# Battery_Gauge_Main_Board.net
KiCad netlist of a schematic drawn in EAGLE
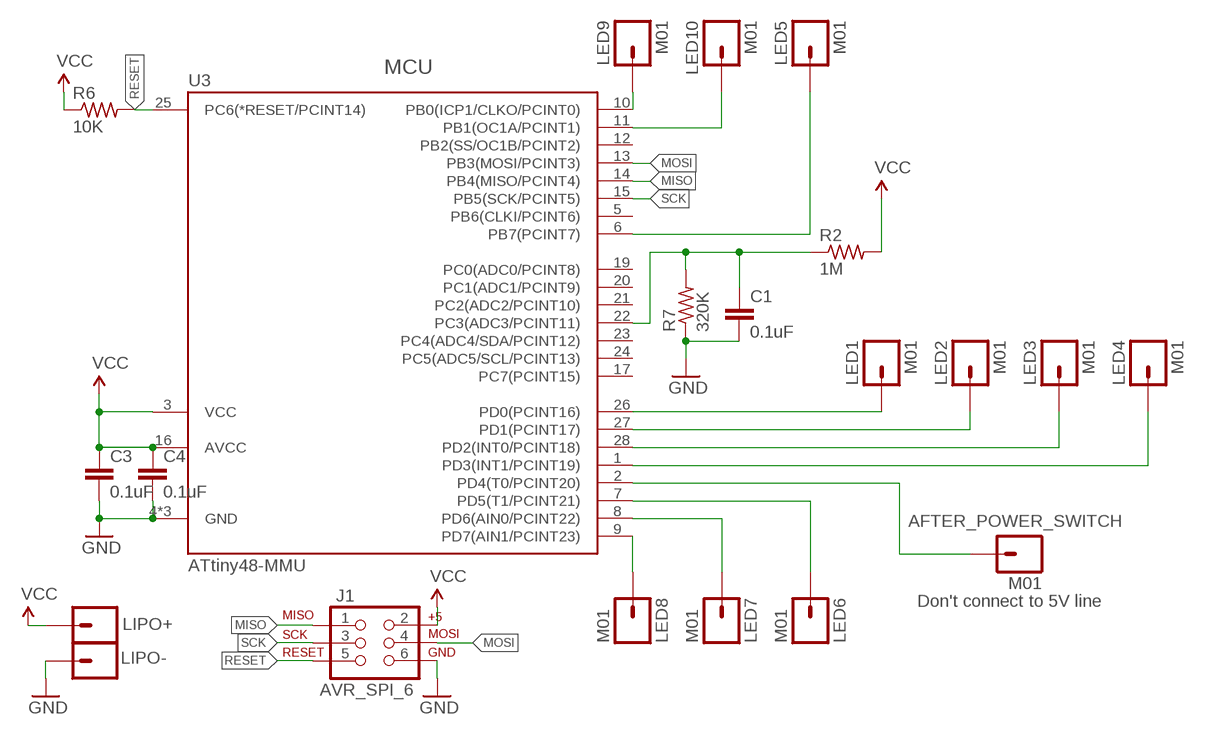
[diagram p0: schematic, sheet 1]

(export (version "E")
  (design (tool "Eeschema 10.0.6"))
  (components
    (comp (ref "AFTER_POWER_SWITCH")
      (value "M01")
      (footprint "eagle-import:1X01_SMD_SM")
      (libsource (lib "eagle-import") (part "M01"))
    )
    (comp (ref "C1")
      (value "0.1uF")
      (footprint "eagle-import:C0603K")
      (libsource (lib "eagle-import") (part "CAP0603"))
    )
    (comp (ref "C3")
      (value "0.1uF")
      (footprint "eagle-import:C0603K")
      (libsource (lib "eagle-import") (part "CAP0603"))
    )
    (comp (ref "C4")
      (value "0.1uF")
      (footprint "eagle-import:C0603K")
      (libsource (lib "eagle-import") (part "CAP0603"))
    )
    (comp (ref "J1")
      (value "AVR_SPI_6")
      (footprint "eagle-import:2X3_2")
      (libsource (lib "eagle-import") (part "AVR_SPI_PRG_6"))
    )
    (comp (ref "LED1")
      (value "M01")
      (footprint "eagle-import:1X01_SMD_SM")
      (libsource (lib "eagle-import") (part "M01"))
    )
    (comp (ref "LED2")
      (value "M01")
      (footprint "eagle-import:1X01_SMD_SM")
      (libsource (lib "eagle-import") (part "M01"))
    )
    (comp (ref "LED3")
      (value "M01")
      (footprint "eagle-import:1X01_SMD_SM")
      (libsource (lib "eagle-import") (part "M01"))
    )
    (comp (ref "LED4")
      (value "M01")
      (footprint "eagle-import:1X01_SMD_SM")
      (libsource (lib "eagle-import") (part "M01"))
    )
    (comp (ref "LED5")
      (value "M01")
      (footprint "eagle-import:1X01_SMD_SM")
      (libsource (lib "eagle-import") (part "M01"))
    )
    (comp (ref "LED6")
      (value "M01")
      (footprint "eagle-import:1X01_SMD_SM")
      (libsource (lib "eagle-import") (part "M01"))
    )
    (comp (ref "LED7")
      (value "M01")
      (footprint "eagle-import:1X01_SMD_SM")
      (libsource (lib "eagle-import") (part "M01"))
    )
    (comp (ref "LED8")
      (value "M01")
      (footprint "eagle-import:1X01_SMD_SM")
      (libsource (lib "eagle-import") (part "M01"))
    )
    (comp (ref "LED9")
      (value "M01")
      (footprint "eagle-import:1X01_SMD_SM")
      (libsource (lib "eagle-import") (part "M01"))
    )
    (comp (ref "LED10")
      (value "M01")
      (footprint "eagle-import:1X01_SMD_SM")
      (libsource (lib "eagle-import") (part "M01"))
    )
    (comp (ref "LIPO+")
      (value "M01SMALL")
      (footprint "eagle-import:1X01_SMD_SMALL")
      (libsource (lib "eagle-import") (part "M01SMALL"))
    )
    (comp (ref "LIPO-")
      (value "M01SMALL")
      (footprint "eagle-import:1X01_SMD_SMALL")
      (libsource (lib "eagle-import") (part "M01SMALL"))
    )
    (comp (ref "R2")
      (value "1M")
      (footprint "eagle-import:R0603_S")
      (libsource (lib "eagle-import") (part "R-US_R0603_S"))
    )
    (comp (ref "R6")
      (value "10K")
      (footprint "eagle-import:R0603_S")
      (libsource (lib "eagle-import") (part "R-US_R0603_S"))
    )
    (comp (ref "R7")
      (value "320K")
      (footprint "eagle-import:R0603_S")
      (libsource (lib "eagle-import") (part "R-US_R0603_S"))
    )
    (comp (ref "U3")
      (value "ATtiny48-MMU")
      (footprint "eagle-import:VQFN-28")
      (libsource (lib "eagle-import") (part "TINY48"))
    )
  )
  (nets
    (net (code "1") (name "GND") (class "Default")
      (node (ref "C1") (pin "2") (pinfunction "2_2") (pintype "passive"))
      (node (ref "C3") (pin "2") (pinfunction "2_2") (pintype "passive"))
      (node (ref "C4") (pin "2") (pinfunction "2_2") (pintype "passive"))
      (node (ref "J1") (pin "6") (pinfunction "6_6") (pintype "passive"))
      (node (ref "LIPO-") (pin "1") (pinfunction "1_1") (pintype "passive"))
      (node (ref "R7") (pin "1") (pinfunction "1_1") (pintype "passive"))
      (node (ref "U3") (pin "18") (pinfunction "GND_18") (pintype "power_in"))
      (node (ref "U3") (pin "29") (pinfunction "GND_29") (pintype "power_in"))
      (node (ref "U3") (pin "4") (pinfunction "GND_4") (pintype "power_in"))
    )
    (net (code "2") (name "MISO") (class "Default")
      (node (ref "J1") (pin "1") (pinfunction "1_1") (pintype "passive"))
      (node (ref "U3") (pin "14") (pinfunction "PB4(MISO/PCINT4)_14") (pintype "bidirectional"))
    )
    (net (code "3") (name "MOSI") (class "Default")
      (node (ref "J1") (pin "4") (pinfunction "4_4") (pintype "passive"))
      (node (ref "U3") (pin "13") (pinfunction "PB3(MOSI/PCINT3)_13") (pintype "bidirectional"))
    )
    (net (code "4") (name "Net-(AFTER_POWER_SWITCH-1)") (class "Default")
      (node (ref "AFTER_POWER_SWITCH") (pin "P$1") (pinfunction "1_P$1") (pintype "passive"))
      (node (ref "U3") (pin "2") (pinfunction "PD4(T0/PCINT20)_2") (pintype "bidirectional"))
    )
    (net (code "5") (name "Net-(LED1-1)") (class "Default")
      (node (ref "LED1") (pin "P$1") (pinfunction "1_P$1") (pintype "passive"))
      (node (ref "U3") (pin "26") (pinfunction "PD0(PCINT16)_26") (pintype "bidirectional"))
    )
    (net (code "6") (name "Net-(LED2-1)") (class "Default")
      (node (ref "LED2") (pin "P$1") (pinfunction "1_P$1") (pintype "passive"))
      (node (ref "U3") (pin "27") (pinfunction "PD1(PCINT17)_27") (pintype "bidirectional"))
    )
    (net (code "7") (name "Net-(LED3-1)") (class "Default")
      (node (ref "LED3") (pin "P$1") (pinfunction "1_P$1") (pintype "passive"))
      (node (ref "U3") (pin "28") (pinfunction "PD2(INT0/PCINT18)_28") (pintype "bidirectional"))
    )
    (net (code "8") (name "Net-(LED4-1)") (class "Default")
      (node (ref "LED4") (pin "P$1") (pinfunction "1_P$1") (pintype "passive"))
      (node (ref "U3") (pin "1") (pinfunction "PD3(INT1/PCINT19)_1") (pintype "bidirectional"))
    )
    (net (code "9") (name "Net-(LED5-1)") (class "Default")
      (node (ref "LED5") (pin "P$1") (pinfunction "1_P$1") (pintype "passive"))
      (node (ref "U3") (pin "6") (pinfunction "PB7(PCINT7)_6") (pintype "bidirectional"))
    )
    (net (code "10") (name "Net-(LED6-1)") (class "Default")
      (node (ref "LED6") (pin "P$1") (pinfunction "1_P$1") (pintype "passive"))
      (node (ref "U3") (pin "7") (pinfunction "PD5(T1/PCINT21)_7") (pintype "bidirectional"))
    )
    (net (code "11") (name "Net-(LED7-1)") (class "Default")
      (node (ref "LED7") (pin "P$1") (pinfunction "1_P$1") (pintype "passive"))
      (node (ref "U3") (pin "8") (pinfunction "PD6(AIN0/PCINT22)_8") (pintype "bidirectional"))
    )
    (net (code "12") (name "Net-(LED8-1)") (class "Default")
      (node (ref "LED8") (pin "P$1") (pinfunction "1_P$1") (pintype "passive"))
      (node (ref "U3") (pin "9") (pinfunction "PD7(AIN1/PCINT23)_9") (pintype "bidirectional"))
    )
    (net (code "13") (name "Net-(LED9-1)") (class "Default")
      (node (ref "LED9") (pin "P$1") (pinfunction "1_P$1") (pintype "passive"))
      (node (ref "U3") (pin "10") (pinfunction "PB0(ICP1/CLKO/PCINT0)_10") (pintype "bidirectional"))
    )
    (net (code "14") (name "Net-(LED10-1)") (class "Default")
      (node (ref "LED10") (pin "P$1") (pinfunction "1_P$1") (pintype "passive"))
      (node (ref "U3") (pin "11") (pinfunction "PB1(OC1A/PCINT1)_11") (pintype "bidirectional"))
    )
    (net (code "15") (name "Net-(U3-PC3(ADC3{slash}PCINT11))") (class "Default")
      (node (ref "C1") (pin "1") (pinfunction "1_1") (pintype "passive"))
      (node (ref "R2") (pin "1") (pinfunction "1_1") (pintype "passive"))
      (node (ref "R7") (pin "2") (pinfunction "2_2") (pintype "passive"))
      (node (ref "U3") (pin "22") (pinfunction "PC3(ADC3/PCINT11)_22") (pintype "bidirectional"))
    )
    (net (code "16") (name "RESET") (class "Default")
      (node (ref "J1") (pin "5") (pinfunction "5_5") (pintype "passive"))
      (node (ref "R6") (pin "2") (pinfunction "2_2") (pintype "passive"))
      (node (ref "U3") (pin "25") (pinfunction "PC6(*RESET/PCINT14)_25") (pintype "bidirectional"))
    )
    (net (code "17") (name "SCK") (class "Default")
      (node (ref "J1") (pin "3") (pinfunction "3_3") (pintype "passive"))
      (node (ref "U3") (pin "15") (pinfunction "PB5(SCK/PCINT5)_15") (pintype "bidirectional"))
    )
    (net (code "18") (name "VCC") (class "Default")
      (node (ref "C3") (pin "1") (pinfunction "1_1") (pintype "passive"))
      (node (ref "C4") (pin "1") (pinfunction "1_1") (pintype "passive"))
      (node (ref "J1") (pin "2") (pinfunction "2_2") (pintype "passive"))
      (node (ref "LIPO+") (pin "1") (pinfunction "1_1") (pintype "passive"))
      (node (ref "R2") (pin "2") (pinfunction "2_2") (pintype "passive"))
      (node (ref "R6") (pin "1") (pinfunction "1_1") (pintype "passive"))
      (node (ref "U3") (pin "16") (pinfunction "AVCC_16") (pintype "power_in"))
      (node (ref "U3") (pin "3") (pinfunction "VCC_3") (pintype "power_in"))
    )
    (net (code "19") (name "unconnected-(U3-PB2(SS{slash}OC1B{slash}PCINT2)-Pad12)") (class "Default")
      (node (ref "U3") (pin "12") (pinfunction "PB2(SS/OC1B/PCINT2)_12") (pintype "bidirectional"))
    )
    (net (code "20") (name "unconnected-(U3-PB6(CLKI{slash}PCINT6)-Pad5)") (class "Default")
      (node (ref "U3") (pin "5") (pinfunction "PB6(CLKI/PCINT6)_5") (pintype "bidirectional"))
    )
    (net (code "21") (name "unconnected-(U3-PC0(ADC0{slash}PCINT8)-Pad19)") (class "Default")
      (node (ref "U3") (pin "19") (pinfunction "PC0(ADC0/PCINT8)_19") (pintype "bidirectional"))
    )
    (net (code "22") (name "unconnected-(U3-PC1(ADC1{slash}PCINT9)-Pad20)") (class "Default")
      (node (ref "U3") (pin "20") (pinfunction "PC1(ADC1/PCINT9)_20") (pintype "bidirectional"))
    )
    (net (code "23") (name "unconnected-(U3-PC2(ADC2{slash}PCINT10)-Pad21)") (class "Default")
      (node (ref "U3") (pin "21") (pinfunction "PC2(ADC2/PCINT10)_21") (pintype "bidirectional"))
    )
    (net (code "24") (name "unconnected-(U3-PC4(ADC4{slash}SDA{slash}PCINT12)-Pad23)") (class "Default")
      (node (ref "U3") (pin "23") (pinfunction "PC4(ADC4/SDA/PCINT12)_23") (pintype "bidirectional"))
    )
    (net (code "25") (name "unconnected-(U3-PC5(ADC5{slash}SCL{slash}PCINT13)-Pad24)") (class "Default")
      (node (ref "U3") (pin "24") (pinfunction "PC5(ADC5/SCL/PCINT13)_24") (pintype "bidirectional"))
    )
    (net (code "26") (name "unconnected-(U3-PC7(PCINT15)-Pad17)") (class "Default")
      (node (ref "U3") (pin "17") (pinfunction "PC7(PCINT15)_17") (pintype "bidirectional"))
    )
  )
)
